# prototipo_final.net
KiCad netlist of a schematic drawn in EAGLE
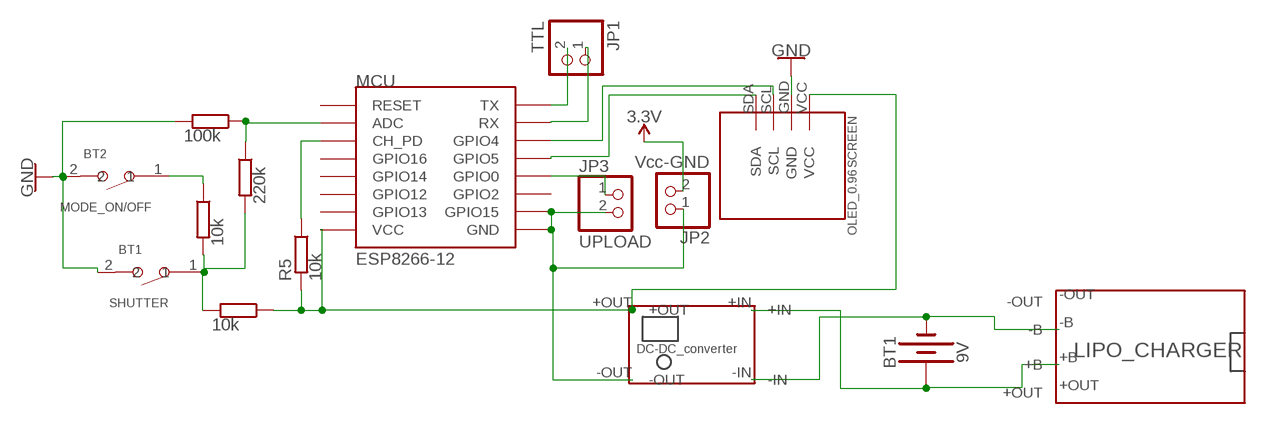
[diagram p0: schematic, sheet 1]

(export (version "E")
  (design (tool "Eeschema 10.0.6"))
  (components
    (comp (ref "BT1")
      (value "9V")
      (footprint "eagle-import:BATTCON_9V")
      (libsource (lib "eagle-import") (part "BATTERY-9V"))
    )
    (comp (ref "JP1")
      (value "TTL")
      (footprint "eagle-import:1X02_90")
      (libsource (lib "eagle-import") (part "PINHD-1X2/90"))
    )
    (comp (ref "JP2")
      (value "Vcc-GND")
      (footprint "eagle-import:1X02_90")
      (libsource (lib "eagle-import") (part "PINHD-1X2/90"))
    )
    (comp (ref "JP3")
      (value "UPLOAD")
      (footprint "eagle-import:1X02_90")
      (libsource (lib "eagle-import") (part "PINHD-1X2/90"))
    )
    (comp (ref "MCU")
      (value "ESP8266-12")
      (footprint "eagle-import:ESP12-SMD")
      (libsource (lib "eagle-import") (part "ESP12SMD"))
    )
    (comp (ref "MODE_ON/OFF")
      (value "BT2")
      (footprint "eagle-import:SW2-2.6-3.0X2.5X1.2+0.4MM")
      (fields (field (name "MPN") "B3U-1000P-2P-SMD"))
      (libsource (lib "eagle-import") (part "SMD-BUTTON(2P-3.0X2.5X1.2+0.4MM)-B3U-1000P-2P-SMD"))
    )
    (comp (ref "R1")
      (value "10k")
      (footprint "eagle-import:SMS-0")
      (libsource (lib "eagle-import") (part "SMS-0"))
    )
    (comp (ref "R2")
      (value "10k")
      (footprint "eagle-import:SMS-0")
      (libsource (lib "eagle-import") (part "SMS-0"))
    )
    (comp (ref "R5")
      (value "10k")
      (footprint "eagle-import:SMS-0")
      (libsource (lib "eagle-import") (part "SMS-0"))
    )
    (comp (ref "R6")
      (value "220k")
      (footprint "eagle-import:SMS-0")
      (libsource (lib "eagle-import") (part "SMS-0"))
    )
    (comp (ref "R7")
      (value "100k")
      (footprint "eagle-import:SMS-0")
      (libsource (lib "eagle-import") (part "SMS-0"))
    )
    (comp (ref "SCREEN")
      (value "OLED_0.96")
      (footprint "eagle-import:OLED_0.96_I2C")
      (libsource (lib "eagle-import") (part "OLED_0.96_I2C"))
    )
    (comp (ref "SHUTTER")
      (value "BT1")
      (footprint "eagle-import:SW2-2.6-3.0X2.5X1.2+0.4MM")
      (fields (field (name "MPN") "B3U-1000P-2P-SMD"))
      (libsource (lib "eagle-import") (part "SMD-BUTTON(2P-3.0X2.5X1.2+0.4MM)-B3U-1000P-2P-SMD"))
    )
    (comp (ref "U$1")
      (value "DC-DC_CONVERTER")
      (footprint "eagle-import:DC-DC_CONVERTER")
      (libsource (lib "eagle-import") (part "DC-DC_CONVERTER"))
    )
    (comp (ref "U$2")
      (value "LIPO_CHARGER")
      (footprint "eagle-import:LIPO-CHARGER")
      (libsource (lib "eagle-import") (part "LIPO_CHARGER"))
    )
  )
  (nets
    (net (code "1") (name "3.3V") (class "Default")
      (node (ref "JP2") (pin "2") (pinfunction "2_2") (pintype "passive"))
    )
    (net (code "2") (name "GND") (class "Default")
      (node (ref "MODE_ON/OFF") (pin "2") (pinfunction "2_2") (pintype "bidirectional"))
      (node (ref "R7") (pin "2") (pinfunction "2_2") (pintype "passive"))
      (node (ref "SCREEN") (pin "GND") (pinfunction "GND_GND") (pintype "bidirectional"))
      (node (ref "SHUTTER") (pin "2") (pinfunction "2_2") (pintype "bidirectional"))
    )
    (net (code "3") (name "Net-(BT1-Pad+)") (class "Default")
      (node (ref "BT1") (pin "+") (pinfunction "+_+") (pintype "power_in"))
      (node (ref "U$1") (pin "+IN") (pinfunction "+IN_+IN") (pintype "bidirectional"))
      (node (ref "U$2") (pin "+B") (pinfunction "+B_+B") (pintype "bidirectional"))
    )
    (net (code "4") (name "Net-(BT1-Pad-)") (class "Default")
      (node (ref "BT1") (pin "-") (pinfunction "-_-") (pintype "power_in"))
      (node (ref "U$1") (pin "-IN") (pinfunction "-IN_-IN") (pintype "bidirectional"))
      (node (ref "U$2") (pin "-B") (pinfunction "-B_-B") (pintype "bidirectional"))
    )
    (net (code "5") (name "Net-(JP2-Pad1)") (class "Default")
      (node (ref "JP2") (pin "1") (pinfunction "1_1") (pintype "passive"))
      (node (ref "JP3") (pin "2") (pinfunction "2_2") (pintype "passive"))
      (node (ref "MCU") (pin "GND") (pinfunction "GND_GND") (pintype "bidirectional"))
      (node (ref "MCU") (pin "GPIO15") (pinfunction "GPIO15_GPIO15") (pintype "bidirectional"))
      (node (ref "U$1") (pin "-OUT") (pinfunction "-OUT_-OUT") (pintype "bidirectional"))
    )
    (net (code "6") (name "Net-(JP3-Pad1)") (class "Default")
      (node (ref "JP3") (pin "1") (pinfunction "1_1") (pintype "passive"))
      (node (ref "MCU") (pin "GPIO0") (pinfunction "GPIO0_GPIO0") (pintype "bidirectional"))
    )
    (net (code "7") (name "Net-(MCU-PadADC)") (class "Default")
      (node (ref "MCU") (pin "ADC") (pinfunction "ADC_ADC") (pintype "bidirectional"))
      (node (ref "R6") (pin "1") (pinfunction "1_1") (pintype "passive"))
      (node (ref "R7") (pin "1") (pinfunction "1_1") (pintype "passive"))
    )
    (net (code "8") (name "Net-(MCU-PadCH_PD)") (class "Default")
      (node (ref "MCU") (pin "CH_PD") (pinfunction "CH_PD_CH_PD") (pintype "bidirectional"))
      (node (ref "R5") (pin "1") (pinfunction "1_1") (pintype "passive"))
    )
    (net (code "9") (name "Net-(MCU-PadGPIO4)") (class "Default")
      (node (ref "MCU") (pin "GPIO4") (pinfunction "GPIO4_GPIO4") (pintype "bidirectional"))
      (node (ref "SCREEN") (pin "SCL") (pinfunction "SCL_SCL") (pintype "bidirectional"))
    )
    (net (code "10") (name "Net-(MCU-PadGPIO5)") (class "Default")
      (node (ref "MCU") (pin "GPIO5") (pinfunction "GPIO5_GPIO5") (pintype "bidirectional"))
      (node (ref "SCREEN") (pin "SDA") (pinfunction "SDA_SDA") (pintype "bidirectional"))
    )
    (net (code "11") (name "Net-(MCU-PadVCC)") (class "Default")
      (node (ref "MCU") (pin "VCC") (pinfunction "VCC_VCC") (pintype "bidirectional"))
      (node (ref "R2") (pin "1") (pinfunction "1_1") (pintype "passive"))
      (node (ref "R5") (pin "2") (pinfunction "2_2") (pintype "passive"))
      (node (ref "SCREEN") (pin "VCC") (pinfunction "VCC_VCC") (pintype "bidirectional"))
      (node (ref "U$1") (pin "+OUT") (pinfunction "+OUT_+OUT") (pintype "bidirectional"))
    )
    (net (code "12") (name "Net-(MCU-RX)") (class "Default")
      (node (ref "JP1") (pin "1") (pinfunction "1_1") (pintype "passive"))
      (node (ref "MCU") (pin "RXD0") (pinfunction "RX_RXD0") (pintype "bidirectional"))
    )
    (net (code "13") (name "Net-(MCU-TX)") (class "Default")
      (node (ref "JP1") (pin "2") (pinfunction "2_2") (pintype "passive"))
      (node (ref "MCU") (pin "TXD0") (pinfunction "TX_TXD0") (pintype "bidirectional"))
    )
    (net (code "14") (name "Net-(MODE_ON/OFF-Pad1)") (class "Default")
      (node (ref "MODE_ON/OFF") (pin "1") (pinfunction "1_1") (pintype "bidirectional"))
      (node (ref "R1") (pin "1") (pinfunction "1_1") (pintype "passive"))
    )
    (net (code "15") (name "Net-(R1-Pad2)") (class "Default")
      (node (ref "R1") (pin "2") (pinfunction "2_2") (pintype "passive"))
      (node (ref "R2") (pin "2") (pinfunction "2_2") (pintype "passive"))
      (node (ref "R6") (pin "2") (pinfunction "2_2") (pintype "passive"))
      (node (ref "SHUTTER") (pin "1") (pinfunction "1_1") (pintype "bidirectional"))
    )
    (net (code "16") (name "unconnected-(MCU-PadGPIO2)") (class "Default")
      (node (ref "MCU") (pin "GPIO2") (pinfunction "GPIO2_GPIO2") (pintype "bidirectional"))
    )
    (net (code "17") (name "unconnected-(MCU-PadGPIO12)") (class "Default")
      (node (ref "MCU") (pin "GPIO12") (pinfunction "GPIO12_GPIO12") (pintype "bidirectional"))
    )
    (net (code "18") (name "unconnected-(MCU-PadGPIO13)") (class "Default")
      (node (ref "MCU") (pin "GPIO13") (pinfunction "GPIO13_GPIO13") (pintype "bidirectional"))
    )
    (net (code "19") (name "unconnected-(MCU-PadGPIO14)") (class "Default")
      (node (ref "MCU") (pin "GPIO14") (pinfunction "GPIO14_GPIO14") (pintype "bidirectional"))
    )
    (net (code "20") (name "unconnected-(MCU-PadGPIO16)") (class "Default")
      (node (ref "MCU") (pin "GPIO16") (pinfunction "GPIO16_GPIO16") (pintype "bidirectional"))
    )
    (net (code "21") (name "unconnected-(MCU-PadRESET)") (class "Default")
      (node (ref "MCU") (pin "RESET") (pinfunction "RESET_RESET") (pintype "bidirectional"))
    )
    (net (code "22") (name "unconnected-(U$2-Pad+OUT)") (class "Default")
      (node (ref "U$2") (pin "+OUT") (pinfunction "+OUT_+OUT") (pintype "bidirectional"))
    )
    (net (code "23") (name "unconnected-(U$2-Pad-OUT)") (class "Default")
      (node (ref "U$2") (pin "-OUT") (pinfunction "-OUT_-OUT") (pintype "bidirectional"))
    )
  )
)
